# Adapter-Stamps-002.net
KiCad netlist of a schematic drawn in EAGLE
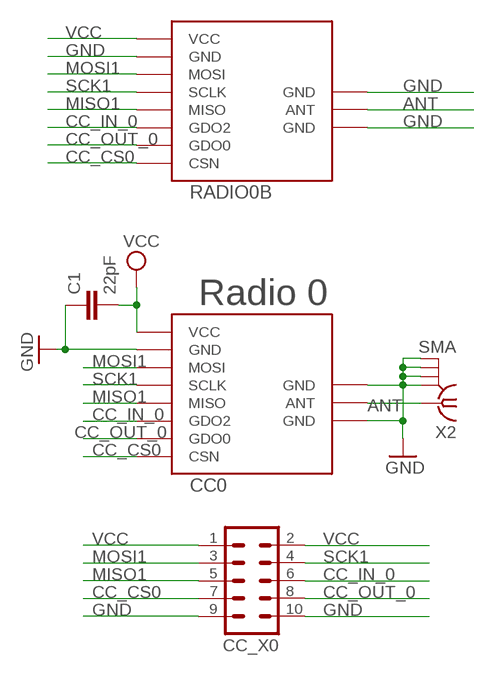
[diagram p0: schematic, sheet 1]

(export (version "E")
  (design (tool "Eeschema 10.0.6"))
  (components
    (comp (ref "C1")
      (value "22pF")
      (footprint "eagle-import:C0805")
      (libsource (lib "eagle-import") (part "C-EUC0805"))
    )
    (comp (ref "CC0")
      (value "CC1101_MODULE1SMD")
      (footprint "eagle-import:CC1101_MODULE1_SMD")
      (libsource (lib "eagle-import") (part "wireless_CC1101_MODULE1SMD"))
    )
    (comp (ref "CC_X0")
      (value "MA05-2")
      (footprint "eagle-import:MA05-2")
      (libsource (lib "eagle-import") (part "MA05-2"))
    )
    (comp (ref "RADIO0B")
      (value "CC1101_MODULE1SMALL")
      (footprint "eagle-import:CC1101_MODULE1_SMD")
      (libsource (lib "eagle-import") (part "CC1101_MODULE1SMALL"))
    )
    (comp (ref "X2")
      (value "SMA")
      (footprint "eagle-import:SMA")
      (libsource (lib "eagle-import") (part "SMA"))
    )
  )
  (nets
    (net (code "1") (name "/ANT") (class "Default")
      (node (ref "CC0") (pin "ANT") (pinfunction "ANT_ANT") (pintype "output"))
      (node (ref "RADIO0B") (pin "ANT") (pinfunction "ANT_ANT") (pintype "output"))
      (node (ref "X2") (pin "1") (pinfunction "1_1") (pintype "passive"))
    )
    (net (code "2") (name "/CC_CS0") (class "Default")
      (node (ref "CC0") (pin "CSN") (pinfunction "CSN_CSN") (pintype "bidirectional"))
      (node (ref "CC_X0") (pin "7") (pinfunction "7_7") (pintype "passive"))
      (node (ref "RADIO0B") (pin "CSN") (pinfunction "CSN_CSN") (pintype "bidirectional"))
    )
    (net (code "3") (name "/CC_IN_0") (class "Default")
      (node (ref "CC0") (pin "GDO2") (pinfunction "GDO2_GDO2") (pintype "bidirectional"))
      (node (ref "CC_X0") (pin "6") (pinfunction "6_6") (pintype "passive"))
      (node (ref "RADIO0B") (pin "GDO2") (pinfunction "GDO2_GDO2") (pintype "bidirectional"))
    )
    (net (code "4") (name "/CC_OUT_0") (class "Default")
      (node (ref "CC0") (pin "GDO0") (pinfunction "GDO0_GDO0") (pintype "bidirectional"))
      (node (ref "CC_X0") (pin "8") (pinfunction "8_8") (pintype "passive"))
      (node (ref "RADIO0B") (pin "GDO0") (pinfunction "GDO0_GDO0") (pintype "bidirectional"))
    )
    (net (code "5") (name "/MISO1") (class "Default")
      (node (ref "CC0") (pin "MISO") (pinfunction "MISO_MISO") (pintype "bidirectional"))
      (node (ref "CC_X0") (pin "5") (pinfunction "5_5") (pintype "passive"))
      (node (ref "RADIO0B") (pin "MISO") (pinfunction "MISO_MISO") (pintype "bidirectional"))
    )
    (net (code "6") (name "/MOSI1") (class "Default")
      (node (ref "CC0") (pin "MOSI") (pinfunction "MOSI_MOSI") (pintype "bidirectional"))
      (node (ref "CC_X0") (pin "3") (pinfunction "3_3") (pintype "passive"))
      (node (ref "RADIO0B") (pin "MOSI") (pinfunction "MOSI_MOSI") (pintype "bidirectional"))
    )
    (net (code "7") (name "/SCK1") (class "Default")
      (node (ref "CC0") (pin "SCLK") (pinfunction "SCLK_SCLK") (pintype "bidirectional"))
      (node (ref "CC_X0") (pin "4") (pinfunction "4_4") (pintype "passive"))
      (node (ref "RADIO0B") (pin "SCLK") (pinfunction "SCLK_SCLK") (pintype "bidirectional"))
    )
    (net (code "8") (name "GND") (class "Default")
      (node (ref "C1") (pin "1") (pinfunction "1_1") (pintype "passive"))
      (node (ref "CC0") (pin "GND@0") (pinfunction "GND_GND@0") (pintype "power_in"))
      (node (ref "CC0") (pin "GND@1") (pinfunction "GND_GND@1") (pintype "power_in"))
      (node (ref "CC0") (pin "GND@2") (pinfunction "GND_GND@2") (pintype "power_in"))
      (node (ref "CC_X0") (pin "10") (pinfunction "10_10") (pintype "passive"))
      (node (ref "CC_X0") (pin "9") (pinfunction "9_9") (pintype "passive"))
      (node (ref "RADIO0B") (pin "GND@0") (pinfunction "GND_GND@0") (pintype "power_in"))
      (node (ref "RADIO0B") (pin "GND@1") (pinfunction "GND_GND@1") (pintype "power_in"))
      (node (ref "RADIO0B") (pin "GND@2") (pinfunction "GND_GND@2") (pintype "power_in"))
      (node (ref "X2") (pin "GND@1") (pinfunction "2_GND@1") (pintype "passive"))
      (node (ref "X2") (pin "GND@2") (pinfunction "3_GND@2") (pintype "passive"))
      (node (ref "X2") (pin "GND@3") (pinfunction "4_GND@3") (pintype "passive"))
      (node (ref "X2") (pin "GND@4") (pinfunction "5_GND@4") (pintype "passive"))
    )
    (net (code "9") (name "VCC") (class "Default")
      (node (ref "C1") (pin "2") (pinfunction "2_2") (pintype "passive"))
      (node (ref "CC0") (pin "VCC") (pinfunction "VCC_VCC") (pintype "power_in"))
      (node (ref "CC_X0") (pin "1") (pinfunction "1_1") (pintype "passive"))
      (node (ref "CC_X0") (pin "2") (pinfunction "2_2") (pintype "passive"))
      (node (ref "RADIO0B") (pin "VCC") (pinfunction "VCC_VCC") (pintype "power_in"))
    )
  )
)
